# MCU_GATEWAY.net
KiCad netlist of a schematic drawn in Altium Designer
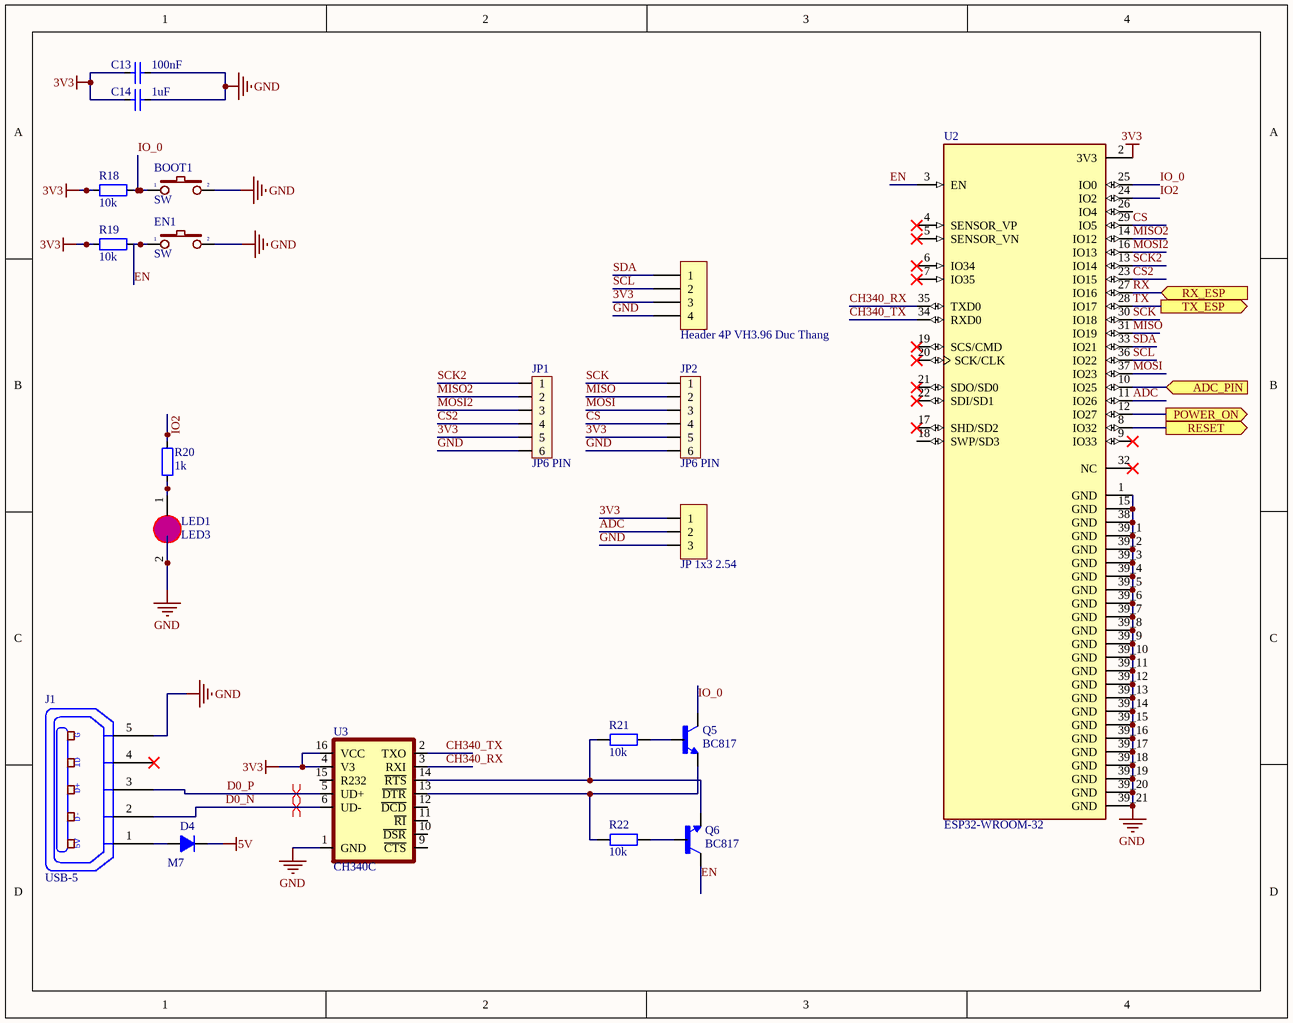
[diagram p0: MCU_GATEWAY.SchDoc]

(export (version "E")
  (design (tool "Eeschema 10.0.6"))
  (components
    (comp (ref "BOOT1")
      (value "SW")
      (footprint "SW-SMD")
      (description "Switch button 2 pin")
      (libsource (lib "My Library") (part "SW2"))
    )
    (comp (ref "C13")
      (value "100nF")
      (footprint "CAP_0805")
      (description "Capacitor")
      (fields (field (name "PUBLISHER") "Altium Limited"))
      (libsource (lib "My Library") (part "CapSMD"))
    )
    (comp (ref "C14")
      (value "1uF")
      (footprint "CAP_0805")
      (description "Capacitor")
      (fields (field (name "PUBLISHER") "Altium Limited"))
      (libsource (lib "My Library") (part "CapSMD"))
    )
    (comp (ref "D4")
      (value "M7")
      (footprint "SMA")
      (description "Diode 1A")
      (libsource (lib "Main") (part "D1A"))
    )
    (comp (ref "EN1")
      (value "SW")
      (footprint "SW-SMD")
      (description "Switch button 2 pin")
      (libsource (lib "My Library") (part "SW2"))
    )
    (comp (ref "H1")
      (value "Header 4P VH3.96 Duc Thang")
      (footprint "CON4")
      (description "Cắm")
      (libsource (lib "Header") (part "Header 4P VH3.96 Duc Thang"))
    )
    (comp (ref "J1")
      (value "USB-5")
      (footprint "USB-M1")
      (fields
        (field (name "MANUFACTURER") "FCI")
        (field (name "MANUFACTURER PART NUMBER") "10118193-0001LF")
        (field (name ".CREATOR") "MM")
        (field (name ".CHECKED PCB") "RF")
        (field (name ".CHECKED SCH") "MM")
      )
      (libsource (lib "My Library 2") (part "USB-5"))
    )
    (comp (ref "JP1") (value "JP6 PIN") (footprint "Header6") (libsource (lib "My Library 2") (part "JP6")))
    (comp (ref "JP2") (value "JP6 PIN") (footprint "Header6") (libsource (lib "My Library 2") (part "JP6")))
    (comp (ref "JP3")
      (value "JP 1x3 2.54")
      (footprint "JP3")
      (description "Cắm")
      (libsource (lib "Jump") (part "JP 1x3 2.54 Cai Thang"))
    )
    (comp (ref "LED1")
      (value "LED3")
      (footprint "LED0805")
      (description "LED SMD 0805")
      (libsource (lib "My Library 2") (part "LED0805"))
    )
    (comp (ref "Q5")
      (value "BC817")
      (footprint "SOT95P240X97-3N")
      (description "Bipolar (BJT) Transistor NPN 45V 500mA 100MHz 250mW Surface Mount TO-236AB")
      (fields (field (name "MF") "Rectron"))
      (libsource (lib "") (part "BC817_1"))
    )
    (comp (ref "Q6")
      (value "BC817")
      (footprint "SOT95P240X97-3N")
      (description "Bipolar (BJT) Transistor NPN 45V 500mA 100MHz 250mW Surface Mount TO-236AB")
      (fields (field (name "MF") "Rectron"))
      (libsource (lib "BC817") (part "BC817"))
    )
    (comp (ref "R18")
      (value "10k")
      (footprint "RES-SMD-0805")
      (description "Resistor SMD")
      (fields
        (field (name "MANUFACTURER") "Generic Components")
        (field (name "PUBLISHER") "Altium Hobart Technology Centre")
      )
      (libsource (lib "My Library") (part "Resistor - SMD"))
    )
    (comp (ref "R19")
      (value "10k")
      (footprint "RES-SMD-0805")
      (description "Resistor SMD")
      (fields
        (field (name "MANUFACTURER") "Generic Components")
        (field (name "PUBLISHER") "Altium Hobart Technology Centre")
      )
      (libsource (lib "My Library") (part "Resistor - SMD"))
    )
    (comp (ref "R20")
      (value "1k")
      (footprint "RES-SMD-0805")
      (description "Resistor SMD")
      (fields
        (field (name "MANUFACTURER") "Generic Components")
        (field (name "PUBLISHER") "Altium Hobart Technology Centre")
      )
      (libsource (lib "My Library") (part "Resistor - SMD"))
    )
    (comp (ref "R21")
      (value "10k")
      (footprint "RES-SMD-0805")
      (description "Resistor SMD")
      (fields
        (field (name "MANUFACTURER") "Generic Components")
        (field (name "PUBLISHER") "Altium Hobart Technology Centre")
      )
      (libsource (lib "My Library") (part "Resistor - SMD"))
    )
    (comp (ref "R22")
      (value "10k")
      (footprint "RES-SMD-0805")
      (description "Resistor SMD")
      (fields
        (field (name "MANUFACTURER") "Generic Components")
        (field (name "PUBLISHER") "Altium Hobart Technology Centre")
      )
      (libsource (lib "My Library") (part "Resistor - SMD"))
    )
    (comp (ref "U2")
      (value "ESP32-WROOM-32")
      (footprint "MODULE_ESP32-WROOM-32")
      (fields (field (name "MF") "Espressif Systems"))
      (libsource (lib "ESP32-WROOM-32") (part "ESP32-WROOM-32"))
    )
    (comp (ref "U3")
      (value "CH340C")
      (footprint "SOP-16")
      (description "USB to serial chip CH340")
      (fields (field (name "MF") "WCH"))
      (libsource (lib "My Library") (part "CH340C"))
    )
  )
  (nets
    (net (code "1") (name "/ADC") (class "Default")
      (node (ref "JP3") (pin "2") (pinfunction "2_2") (pintype "passive"))
      (node (ref "U2") (pin "11") (pinfunction "IO26_11") (pintype "bidirectional"))
    )
    (net (code "2") (name "/ADC_PIN") (class "Default")
      (node (ref "U2") (pin "10") (pinfunction "IO25_10") (pintype "bidirectional"))
    )
    (net (code "3") (name "/CH340_RX") (class "Default")
      (node (ref "U2") (pin "35") (pinfunction "TXD0_35") (pintype "bidirectional"))
      (node (ref "U3") (pin "3") (pinfunction "RXI_3") (pintype "bidirectional"))
    )
    (net (code "4") (name "/CH340_TX") (class "Default")
      (node (ref "U2") (pin "34") (pinfunction "RXD0_34") (pintype "bidirectional"))
      (node (ref "U3") (pin "2") (pinfunction "TXO_2") (pintype "bidirectional"))
    )
    (net (code "5") (name "/CS") (class "Default")
      (node (ref "JP2") (pin "4") (pinfunction "4_4") (pintype "passive"))
      (node (ref "U2") (pin "29") (pinfunction "IO5_29") (pintype "bidirectional"))
    )
    (net (code "6") (name "/CS2") (class "Default")
      (node (ref "JP1") (pin "4") (pinfunction "4_4") (pintype "passive"))
      (node (ref "U2") (pin "23") (pinfunction "IO15_23") (pintype "bidirectional"))
    )
    (net (code "7") (name "/D0_N") (class "Default")
      (node (ref "J1") (pin "2") (pinfunction "P2_2") (pintype "passive"))
      (node (ref "U3") (pin "6") (pinfunction "UD-_6") (pintype "bidirectional"))
    )
    (net (code "8") (name "/D0_P") (class "Default")
      (node (ref "J1") (pin "3") (pinfunction "P3_3") (pintype "passive"))
      (node (ref "U3") (pin "5") (pinfunction "UD+_5") (pintype "bidirectional"))
    )
    (net (code "9") (name "/EN") (class "Default")
      (node (ref "EN1") (pin "1") (pinfunction "1_1") (pintype "passive"))
      (node (ref "Q6") (pin "3") (pinfunction "C_3") (pintype "passive"))
      (node (ref "R19") (pin "2") (pinfunction "2_2") (pintype "passive"))
      (node (ref "U2") (pin "3") (pinfunction "EN_3") (pintype "input"))
    )
    (net (code "10") (name "/IO2") (class "Default")
      (node (ref "R20") (pin "1") (pinfunction "1_1") (pintype "passive"))
      (node (ref "U2") (pin "24") (pinfunction "IO2_24") (pintype "bidirectional"))
    )
    (net (code "11") (name "/IO_0") (class "Default")
      (node (ref "BOOT1") (pin "1") (pinfunction "1_1") (pintype "passive"))
      (node (ref "Q5") (pin "3") (pinfunction "C_3") (pintype "passive"))
      (node (ref "R18") (pin "2") (pinfunction "2_2") (pintype "passive"))
      (node (ref "U2") (pin "25") (pinfunction "IO0_25") (pintype "bidirectional"))
    )
    (net (code "12") (name "/MISO") (class "Default")
      (node (ref "JP2") (pin "2") (pinfunction "2_2") (pintype "passive"))
      (node (ref "U2") (pin "31") (pinfunction "IO19_31") (pintype "bidirectional"))
    )
    (net (code "13") (name "/MISO2") (class "Default")
      (node (ref "JP1") (pin "2") (pinfunction "2_2") (pintype "passive"))
      (node (ref "U2") (pin "14") (pinfunction "IO12_14") (pintype "bidirectional"))
    )
    (net (code "14") (name "/MOSI") (class "Default")
      (node (ref "JP2") (pin "3") (pinfunction "3_3") (pintype "passive"))
      (node (ref "U2") (pin "37") (pinfunction "IO23_37") (pintype "bidirectional"))
    )
    (net (code "15") (name "/MOSI2") (class "Default")
      (node (ref "JP1") (pin "3") (pinfunction "3_3") (pintype "passive"))
      (node (ref "U2") (pin "16") (pinfunction "IO13_16") (pintype "bidirectional"))
    )
    (net (code "16") (name "/POWER_ON") (class "Default")
      (node (ref "U2") (pin "12") (pinfunction "IO27_12") (pintype "bidirectional"))
    )
    (net (code "17") (name "/RESET") (class "Default")
      (node (ref "U2") (pin "8") (pinfunction "IO32_8") (pintype "bidirectional"))
    )
    (net (code "18") (name "/RX") (class "Default")
      (node (ref "U2") (pin "27") (pinfunction "IO16_27") (pintype "bidirectional"))
    )
    (net (code "19") (name "/SCK") (class "Default")
      (node (ref "JP2") (pin "1") (pinfunction "1_1") (pintype "passive"))
      (node (ref "U2") (pin "30") (pinfunction "IO18_30") (pintype "bidirectional"))
    )
    (net (code "20") (name "/SCK2") (class "Default")
      (node (ref "JP1") (pin "1") (pinfunction "1_1") (pintype "passive"))
      (node (ref "U2") (pin "13") (pinfunction "IO14_13") (pintype "bidirectional"))
    )
    (net (code "21") (name "/SCL") (class "Default")
      (node (ref "H1") (pin "2") (pinfunction "2_2") (pintype "passive"))
      (node (ref "U2") (pin "36") (pinfunction "IO22_36") (pintype "bidirectional"))
    )
    (net (code "22") (name "/SDA") (class "Default")
      (node (ref "H1") (pin "1") (pinfunction "1_1") (pintype "passive"))
      (node (ref "U2") (pin "33") (pinfunction "IO21_33") (pintype "bidirectional"))
    )
    (net (code "23") (name "/TX") (class "Default")
      (node (ref "U2") (pin "28") (pinfunction "IO17_28") (pintype "bidirectional"))
    )
    (net (code "24") (name "3V3") (class "Default")
      (node (ref "C13") (pin "1") (pinfunction "1_1") (pintype "passive"))
      (node (ref "C14") (pin "1") (pinfunction "1_1") (pintype "passive"))
      (node (ref "H1") (pin "3") (pinfunction "3_3") (pintype "passive"))
      (node (ref "JP1") (pin "5") (pinfunction "5_5") (pintype "passive"))
      (node (ref "JP2") (pin "5") (pinfunction "5_5") (pintype "passive"))
      (node (ref "JP3") (pin "1") (pinfunction "1_1") (pintype "passive"))
      (node (ref "R18") (pin "1") (pinfunction "1_1") (pintype "passive"))
      (node (ref "R19") (pin "1") (pinfunction "1_1") (pintype "passive"))
      (node (ref "U2") (pin "2") (pinfunction "3V3_2") (pintype "power_in"))
      (node (ref "U3") (pin "16") (pinfunction "VCC_16") (pintype "bidirectional"))
      (node (ref "U3") (pin "4") (pinfunction "V3_4") (pintype "bidirectional"))
    )
    (net (code "25") (name "5V") (class "Default")
      (node (ref "D4") (pin "2") (pinfunction "K_2") (pintype "passive"))
    )
    (net (code "26") (name "GND") (class "Default")
      (node (ref "BOOT1") (pin "2") (pinfunction "2_2") (pintype "passive"))
      (node (ref "C13") (pin "2") (pinfunction "2_2") (pintype "passive"))
      (node (ref "C14") (pin "2") (pinfunction "2_2") (pintype "passive"))
      (node (ref "EN1") (pin "2") (pinfunction "2_2") (pintype "passive"))
      (node (ref "H1") (pin "4") (pinfunction "4_4") (pintype "passive"))
      (node (ref "J1") (pin "5") (pinfunction "P5_5") (pintype "passive"))
      (node (ref "JP1") (pin "6") (pinfunction "6_6") (pintype "passive"))
      (node (ref "JP2") (pin "6") (pinfunction "6_6") (pintype "passive"))
      (node (ref "JP3") (pin "3") (pinfunction "3_3") (pintype "passive"))
      (node (ref "LED1") (pin "2") (pinfunction "K_2") (pintype "passive"))
      (node (ref "U2") (pin "1") (pinfunction "GND_1") (pintype "power_in"))
      (node (ref "U2") (pin "15") (pinfunction "GND_15") (pintype "power_in"))
      (node (ref "U2") (pin "38") (pinfunction "GND_38") (pintype "power_in"))
      (node (ref "U2") (pin "39_1") (pinfunction "GND_39_1") (pintype "power_in"))
      (node (ref "U2") (pin "39_10") (pinfunction "GND_39_10") (pintype "power_in"))
      (node (ref "U2") (pin "39_11") (pinfunction "GND_39_11") (pintype "power_in"))
      (node (ref "U2") (pin "39_12") (pinfunction "GND_39_12") (pintype "power_in"))
      (node (ref "U2") (pin "39_13") (pinfunction "GND_39_13") (pintype "power_in"))
      (node (ref "U2") (pin "39_14") (pinfunction "GND_39_14") (pintype "power_in"))
      (node (ref "U2") (pin "39_15") (pinfunction "GND_39_15") (pintype "power_in"))
      (node (ref "U2") (pin "39_16") (pinfunction "GND_39_16") (pintype "power_in"))
      (node (ref "U2") (pin "39_17") (pinfunction "GND_39_17") (pintype "power_in"))
      (node (ref "U2") (pin "39_18") (pinfunction "GND_39_18") (pintype "power_in"))
      (node (ref "U2") (pin "39_19") (pinfunction "GND_39_19") (pintype "power_in"))
      (node (ref "U2") (pin "39_2") (pinfunction "GND_39_2") (pintype "power_in"))
      (node (ref "U2") (pin "39_20") (pinfunction "GND_39_20") (pintype "power_in"))
      (node (ref "U2") (pin "39_21") (pinfunction "GND_39_21") (pintype "power_in"))
      (node (ref "U2") (pin "39_3") (pinfunction "GND_39_3") (pintype "power_in"))
      (node (ref "U2") (pin "39_4") (pinfunction "GND_39_4") (pintype "power_in"))
      (node (ref "U2") (pin "39_5") (pinfunction "GND_39_5") (pintype "power_in"))
      (node (ref "U2") (pin "39_6") (pinfunction "GND_39_6") (pintype "power_in"))
      (node (ref "U2") (pin "39_7") (pinfunction "GND_39_7") (pintype "power_in"))
      (node (ref "U2") (pin "39_8") (pinfunction "GND_39_8") (pintype "power_in"))
      (node (ref "U2") (pin "39_9") (pinfunction "GND_39_9") (pintype "power_in"))
      (node (ref "U3") (pin "1") (pinfunction "GND_1") (pintype "bidirectional"))
    )
    (net (code "27") (name "Net-(D4-A)") (class "Default")
      (node (ref "D4") (pin "1") (pinfunction "A_1") (pintype "passive"))
      (node (ref "J1") (pin "1") (pinfunction "P1_1") (pintype "passive"))
    )
    (net (code "28") (name "Net-(LED1-A)") (class "Default")
      (node (ref "LED1") (pin "1") (pinfunction "A_1") (pintype "passive"))
      (node (ref "R20") (pin "2") (pinfunction "2_2") (pintype "passive"))
    )
    (net (code "29") (name "Net-(Q5-B)") (class "Default")
      (node (ref "Q5") (pin "1") (pinfunction "B_1") (pintype "passive"))
      (node (ref "R21") (pin "2") (pinfunction "2_2") (pintype "passive"))
    )
    (net (code "30") (name "Net-(Q5-E)") (class "Default")
      (node (ref "Q5") (pin "2") (pinfunction "E_2") (pintype "passive"))
      (node (ref "R22") (pin "1") (pinfunction "1_1") (pintype "passive"))
      (node (ref "U3") (pin "13") (pinfunction "~{DTR}_13") (pintype "bidirectional"))
    )
    (net (code "31") (name "Net-(Q6-B)") (class "Default")
      (node (ref "Q6") (pin "1") (pinfunction "B_1") (pintype "passive"))
      (node (ref "R22") (pin "2") (pinfunction "2_2") (pintype "passive"))
    )
    (net (code "32") (name "Net-(Q6-E)") (class "Default")
      (node (ref "Q6") (pin "2") (pinfunction "E_2") (pintype "passive"))
      (node (ref "R21") (pin "1") (pinfunction "1_1") (pintype "passive"))
      (node (ref "U3") (pin "14") (pinfunction "~{RTS}_14") (pintype "bidirectional"))
    )
    (net (code "33") (name "unconnected-(J1-P4-Pad4)") (class "Default")
      (node (ref "J1") (pin "4") (pinfunction "P4_4") (pintype "passive+no_connect"))
    )
    (net (code "34") (name "unconnected-(U2-IO4-Pad26)") (class "Default")
      (node (ref "U2") (pin "26") (pinfunction "IO4_26") (pintype "bidirectional"))
    )
    (net (code "35") (name "unconnected-(U2-IO33-Pad9)") (class "Default")
      (node (ref "U2") (pin "9") (pinfunction "IO33_9") (pintype "bidirectional+no_connect"))
    )
    (net (code "36") (name "unconnected-(U2-IO34-Pad6)") (class "Default")
      (node (ref "U2") (pin "6") (pinfunction "IO34_6") (pintype "input+no_connect"))
    )
    (net (code "37") (name "unconnected-(U2-IO35-Pad7)") (class "Default")
      (node (ref "U2") (pin "7") (pinfunction "IO35_7") (pintype "input+no_connect"))
    )
    (net (code "38") (name "unconnected-(U2-NC-Pad32)") (class "Default")
      (node (ref "U2") (pin "32") (pinfunction "NC_32") (pintype "passive+no_connect"))
    )
    (net (code "39") (name "unconnected-(U2-SCK{slash}CLK-Pad20)") (class "Default")
      (node (ref "U2") (pin "20") (pinfunction "SCK/CLK_20") (pintype "bidirectional+no_connect"))
    )
    (net (code "40") (name "unconnected-(U2-SCS{slash}CMD-Pad19)") (class "Default")
      (node (ref "U2") (pin "19") (pinfunction "SCS/CMD_19") (pintype "bidirectional+no_connect"))
    )
    (net (code "41") (name "unconnected-(U2-SDI{slash}SD1-Pad22)") (class "Default")
      (node (ref "U2") (pin "22") (pinfunction "SDI/SD1_22") (pintype "bidirectional+no_connect"))
    )
    (net (code "42") (name "unconnected-(U2-SDO{slash}SD0-Pad21)") (class "Default")
      (node (ref "U2") (pin "21") (pinfunction "SDO/SD0_21") (pintype "bidirectional+no_connect"))
    )
    (net (code "43") (name "unconnected-(U2-SENSOR_VN-Pad5)") (class "Default")
      (node (ref "U2") (pin "5") (pinfunction "SENSOR_VN_5") (pintype "input+no_connect"))
    )
    (net (code "44") (name "unconnected-(U2-SENSOR_VP-Pad4)") (class "Default")
      (node (ref "U2") (pin "4") (pinfunction "SENSOR_VP_4") (pintype "input+no_connect"))
    )
    (net (code "45") (name "unconnected-(U2-SHD{slash}SD2-Pad17)") (class "Default")
      (node (ref "U2") (pin "17") (pinfunction "SHD/SD2_17") (pintype "bidirectional+no_connect"))
    )
    (net (code "46") (name "unconnected-(U2-SWP{slash}SD3-Pad18)") (class "Default")
      (node (ref "U2") (pin "18") (pinfunction "SWP/SD3_18") (pintype "bidirectional"))
    )
    (net (code "47") (name "unconnected-(U3-R232-Pad15)") (class "Default")
      (node (ref "U3") (pin "15") (pinfunction "R232_15") (pintype "bidirectional"))
    )
    (net (code "48") (name "unconnected-(U3-~{CTS}-Pad9)") (class "Default")
      (node (ref "U3") (pin "9") (pinfunction "~{CTS}_9") (pintype "bidirectional"))
    )
    (net (code "49") (name "unconnected-(U3-~{DCD}-Pad12)") (class "Default")
      (node (ref "U3") (pin "12") (pinfunction "~{DCD}_12") (pintype "bidirectional"))
    )
    (net (code "50") (name "unconnected-(U3-~{DSR}-Pad10)") (class "Default")
      (node (ref "U3") (pin "10") (pinfunction "~{DSR}_10") (pintype "bidirectional"))
    )
    (net (code "51") (name "unconnected-(U3-~{RI}-Pad11)") (class "Default")
      (node (ref "U3") (pin "11") (pinfunction "~{RI}_11") (pintype "bidirectional"))
    )
  )
)
